# STM32.net
KiCad netlist of a schematic drawn in Altium Designer
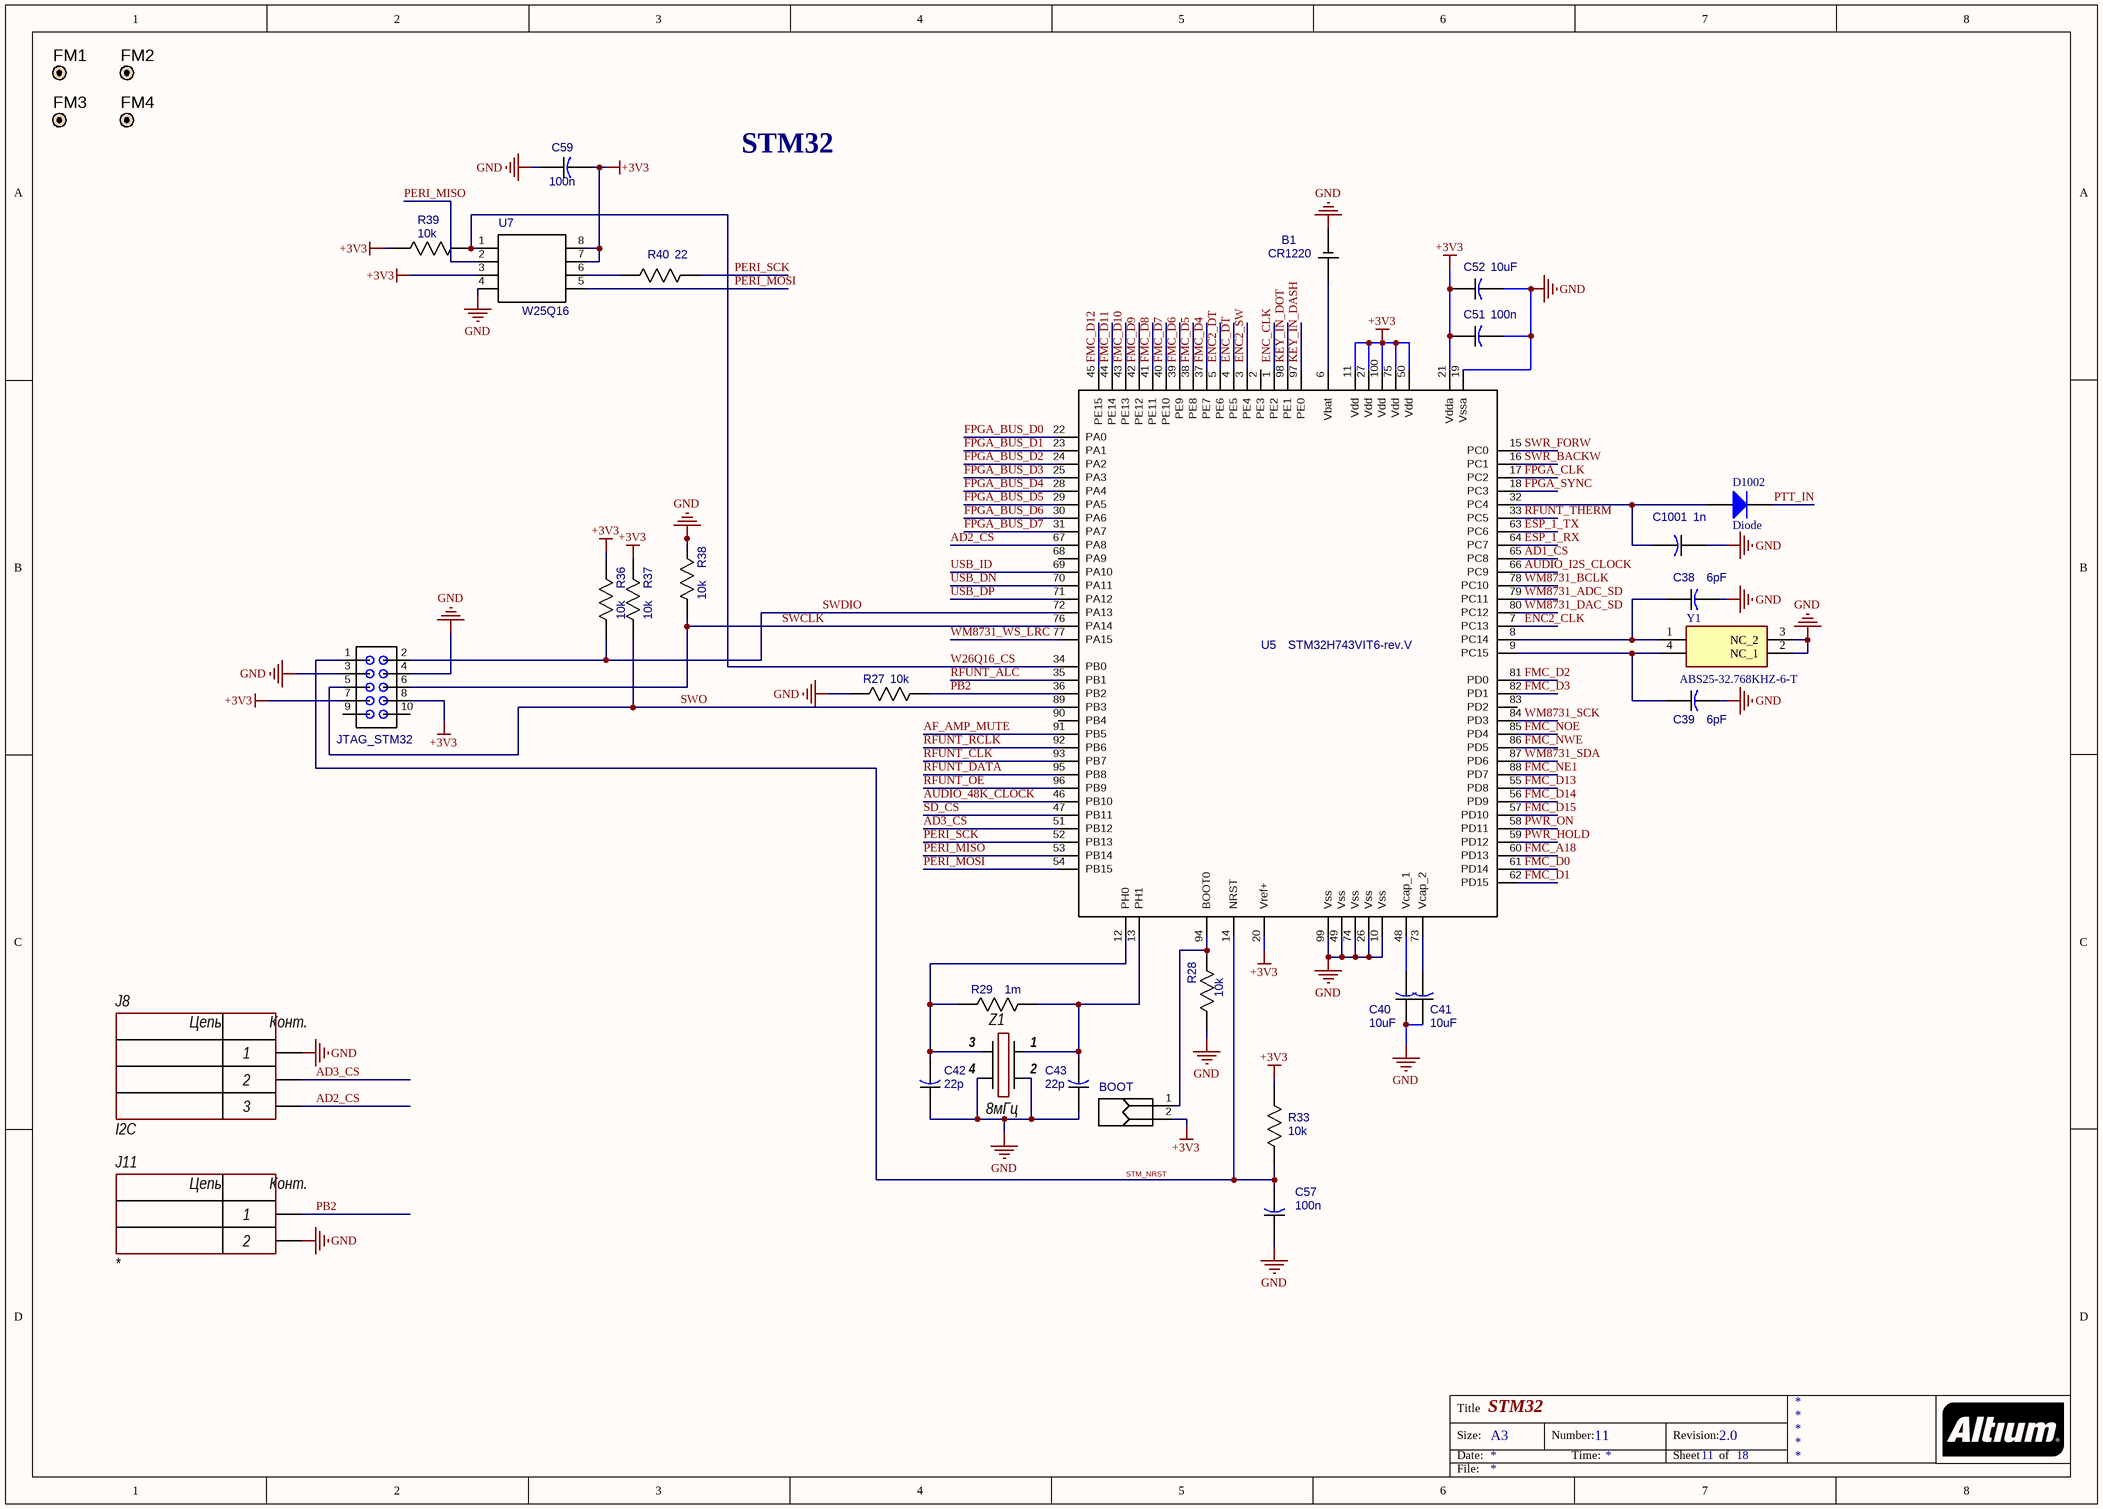
[diagram p0: STM32.SchDoc]

(export (version "E")
  (design (tool "Eeschema 10.0.6"))
  (components
    (comp (ref "B1")
      (value "CR1220")
      (footprint "CR1220")
      (description "BR1632A/FA")
      (fields (field (name "Comment") "CR1220 +"))
      (libsource (lib "*") (part "BR1632A/FA"))
    )
    (comp (ref "BOOT")
      (value "~")
      (footprint "51022-0200")
      (description "2 Pin")
      (libsource (lib "*") (part "51022-0200"))
    )
    (comp (ref "C38")
      (value "6pF")
      (footprint "CAP_0805")
      (description "CAP_0805")
      (libsource (lib "*") (part "CAP_0805"))
    )
    (comp (ref "C39")
      (value "6pF")
      (footprint "CAP_0805")
      (description "CAP_0805")
      (libsource (lib "*") (part "CAP_0805"))
    )
    (comp (ref "C40")
      (value "10uF")
      (footprint "CAP_0805")
      (description "CAP_0805")
      (libsource (lib "*") (part "CAP_0805"))
    )
    (comp (ref "C41")
      (value "10uF")
      (footprint "CAP_0805")
      (description "CAP_0805")
      (libsource (lib "*") (part "CAP_0805"))
    )
    (comp (ref "C42")
      (value "22p")
      (footprint "CH0805C")
      (description "CAP_0805")
      (libsource (lib "*") (part "CAP_0805"))
    )
    (comp (ref "C43")
      (value "22p")
      (footprint "CH0805C")
      (description "CAP_0805")
      (libsource (lib "*") (part "CAP_0805"))
    )
    (comp (ref "C51")
      (value "100n")
      (footprint "CAP_0805")
      (description "CAP_0805")
      (libsource (lib "*") (part "CAP_0805"))
    )
    (comp (ref "C52")
      (value "10uF")
      (footprint "CAP_0805")
      (description "CAP_0805")
      (libsource (lib "*") (part "CAP_0805"))
    )
    (comp (ref "C57")
      (value "100n")
      (footprint "CAP_0805")
      (description "CAP_0805")
      (libsource (lib "*") (part "CAP_0805"))
    )
    (comp (ref "C59")
      (value "100n")
      (footprint "CAP_0805")
      (description "CAP_0805")
      (libsource (lib "*") (part "CAP_0805"))
    )
    (comp (ref "C1001")
      (value "1n")
      (footprint "CAP_0805")
      (description "CAP_0805")
      (libsource (lib "*") (part "CAP_0805"))
    )
    (comp (ref "D1002")
      (value "Diode")
      (footprint "C1206")
      (description "Default Diode")
      (fields (field (name "PUBLISHER") "Altium Limited"))
      (libsource (lib "Miscellaneous Devices") (part "Diode"))
    )
    (comp (ref "FM1") (value "FM1") (footprint "FM") (libsource (lib "Connectors") (part "FM")))
    (comp (ref "FM2") (value "FM1") (footprint "FM") (libsource (lib "Connectors") (part "FM")))
    (comp (ref "FM3") (value "FM1") (footprint "FM") (libsource (lib "Connectors") (part "FM")))
    (comp (ref "FM4") (value "FM1") (footprint "FM") (libsource (lib "Connectors") (part "FM")))
    (comp (ref "J8")
      (value "I2C")
      (footprint "custom:CON: CWF-3")
      (libsource (lib "Connectors") (part "3-Connector"))
    )
    (comp (ref "J11")
      (value "*")
      (footprint "custom:CON: CWF-2")
      (libsource (lib "Connectors") (part "2-Connector"))
    )
    (comp (ref "JTAG_STM32")
      (value "~")
      (footprint "IDC10")
      (description "2*5 Pin")
      (libsource (lib "*") (part "IDC10"))
    )
    (comp (ref "R27")
      (value "10k")
      (footprint "RES_0805")
      (description "RES_0805")
      (libsource (lib "*") (part "RES_0805"))
    )
    (comp (ref "R28")
      (value "10k")
      (footprint "RES_0805")
      (description "RES_0805")
      (libsource (lib "*") (part "RES_0805"))
    )
    (comp (ref "R29")
      (value "1m")
      (footprint "RES_0805")
      (description "RES_0805")
      (libsource (lib "*") (part "RES_0805"))
    )
    (comp (ref "R33")
      (value "10k")
      (footprint "RES_0805")
      (description "RES_0805")
      (libsource (lib "*") (part "RES_0805"))
    )
    (comp (ref "R36")
      (value "10k")
      (footprint "RES_0805")
      (description "RES_0805")
      (libsource (lib "*") (part "RES_0805"))
    )
    (comp (ref "R37")
      (value "10k")
      (footprint "RES_0805")
      (description "RES_0805")
      (libsource (lib "*") (part "RES_0805"))
    )
    (comp (ref "R38")
      (value "10k")
      (footprint "RES_0805")
      (description "RES_0805")
      (libsource (lib "*") (part "RES_0805"))
    )
    (comp (ref "R39")
      (value "10k")
      (footprint "RES_0805")
      (description "RES_0805")
      (libsource (lib "*") (part "RES_0805"))
    )
    (comp (ref "R40")
      (value "22")
      (footprint "RES_0805")
      (description "RES_0805")
      (libsource (lib "*") (part "RES_0805"))
    )
    (comp (ref "U5")
      (value "STM32H743VIT6-rev.V")
      (footprint "STM32H743VIT6")
      (description "STM32H743VIT6")
      (libsource (lib "*") (part "STM32H743VIT6"))
    )
    (comp (ref "U7") (value "W25Q16") (footprint "SOIC-8-1") (libsource (lib "*") (part "W25Q16")))
    (comp (ref "Y1")
      (value "ABS25-32.768KHZ-6-T")
      (footprint "SamacSys:ABS25")
      (description "Crystal or Oscillator")
      (fields
        (field (name "MOUSER PART NUMBER") "815-ABS25-32.768K6-T")
        (field (name "RS PART NUMBER") "1712795P")
      )
      (libsource (lib "*") (part "ABS25-32.768KHZ-6-T"))
    )
    (comp (ref "Z1")
      (value "8мГц")
      (footprint "custom:OSC: 3225")
      (libsource (lib "Discrete") (part "Generator"))
    )
  )
  (nets
    (net (code "1") (name "+3V3") (class "Default")
      (node (ref "BOOT") (pin "2") (pinfunction "2_2") (pintype "passive"))
      (node (ref "C51") (pin "1") (pinfunction "1_1") (pintype "passive"))
      (node (ref "C52") (pin "1") (pinfunction "1_1") (pintype "passive"))
      (node (ref "C59") (pin "2") (pinfunction "2_2") (pintype "passive"))
      (node (ref "JTAG_STM32") (pin "7") (pinfunction "7_7") (pintype "passive"))
      (node (ref "JTAG_STM32") (pin "8") (pinfunction "8_8") (pintype "passive"))
      (node (ref "R33") (pin "2") (pinfunction "2_2") (pintype "passive"))
      (node (ref "R36") (pin "1") (pinfunction "1_1") (pintype "passive"))
      (node (ref "R37") (pin "1") (pinfunction "1_1") (pintype "passive"))
      (node (ref "R39") (pin "1") (pinfunction "1_1") (pintype "passive"))
      (node (ref "U5") (pin "100") (pinfunction "Vdd_100") (pintype "passive"))
      (node (ref "U5") (pin "11") (pinfunction "Vdd_11") (pintype "passive"))
      (node (ref "U5") (pin "20") (pinfunction "Vref+_20") (pintype "passive"))
      (node (ref "U5") (pin "21") (pinfunction "Vdda_21") (pintype "passive"))
      (node (ref "U5") (pin "27") (pinfunction "Vdd_27") (pintype "passive"))
      (node (ref "U5") (pin "50") (pinfunction "Vdd_50") (pintype "passive"))
      (node (ref "U5") (pin "75") (pinfunction "Vdd_75") (pintype "passive"))
      (node (ref "U7") (pin "3") (pinfunction "WP_3") (pintype "passive"))
      (node (ref "U7") (pin "7") (pinfunction "HOLD_7") (pintype "passive"))
      (node (ref "U7") (pin "8") (pinfunction "VCC_8") (pintype "passive"))
    )
    (net (code "2") (name "/AD1_CS") (class "Default")
      (node (ref "U5") (pin "65") (pinfunction "PC8_65") (pintype "passive"))
    )
    (net (code "3") (name "/AD2_CS") (class "Default")
      (node (ref "J8") (pin "3") (pinfunction "3_3") (pintype "power_in"))
      (node (ref "U5") (pin "67") (pinfunction "PA8_67") (pintype "passive"))
    )
    (net (code "4") (name "/AD3_CS") (class "Default")
      (node (ref "J8") (pin "2") (pinfunction "2_2") (pintype "passive"))
      (node (ref "U5") (pin "51") (pinfunction "PB12_51") (pintype "passive"))
    )
    (net (code "5") (name "/AF_AMP_MUTE") (class "Default")
      (node (ref "U5") (pin "91") (pinfunction "PB5_91") (pintype "passive"))
    )
    (net (code "6") (name "/AUDIO_48K_CLOCK") (class "Default")
      (node (ref "U5") (pin "46") (pinfunction "PB10_46") (pintype "passive"))
    )
    (net (code "7") (name "/AUDIO_I2S_CLOCK") (class "Default")
      (node (ref "U5") (pin "66") (pinfunction "PC9_66") (pintype "passive"))
    )
    (net (code "8") (name "/ENC2_CLK") (class "Default")
      (node (ref "U5") (pin "7") (pinfunction "PC13_7") (pintype "passive"))
    )
    (net (code "9") (name "/ENC2_DT") (class "Default")
      (node (ref "U5") (pin "5") (pinfunction "PE6_5") (pintype "passive"))
    )
    (net (code "10") (name "/ENC2_SW") (class "Default")
      (node (ref "U5") (pin "3") (pinfunction "PE4_3") (pintype "passive"))
    )
    (net (code "11") (name "/ENC_CLK") (class "Default")
      (node (ref "U5") (pin "1") (pinfunction "PE2_1") (pintype "passive"))
    )
    (net (code "12") (name "/ENC_DT") (class "Default")
      (node (ref "U5") (pin "4") (pinfunction "PE5_4") (pintype "passive"))
    )
    (net (code "13") (name "/ESP_1_RX") (class "Default")
      (node (ref "U5") (pin "64") (pinfunction "PC7_64") (pintype "passive"))
    )
    (net (code "14") (name "/ESP_1_TX") (class "Default")
      (node (ref "U5") (pin "63") (pinfunction "PC6_63") (pintype "passive"))
    )
    (net (code "15") (name "/FMC_A18") (class "Default")
      (node (ref "U5") (pin "60") (pinfunction "PD13_60") (pintype "passive"))
    )
    (net (code "16") (name "/FMC_D0") (class "Default")
      (node (ref "U5") (pin "61") (pinfunction "PD14_61") (pintype "passive"))
    )
    (net (code "17") (name "/FMC_D1") (class "Default")
      (node (ref "U5") (pin "62") (pinfunction "PD15_62") (pintype "passive"))
    )
    (net (code "18") (name "/FMC_D2") (class "Default")
      (node (ref "U5") (pin "81") (pinfunction "PD0_81") (pintype "passive"))
    )
    (net (code "19") (name "/FMC_D3") (class "Default")
      (node (ref "U5") (pin "82") (pinfunction "PD1_82") (pintype "passive"))
    )
    (net (code "20") (name "/FMC_D4") (class "Default")
      (node (ref "U5") (pin "37") (pinfunction "PE7_37") (pintype "passive"))
    )
    (net (code "21") (name "/FMC_D5") (class "Default")
      (node (ref "U5") (pin "38") (pinfunction "PE8_38") (pintype "passive"))
    )
    (net (code "22") (name "/FMC_D6") (class "Default")
      (node (ref "U5") (pin "39") (pinfunction "PE9_39") (pintype "passive"))
    )
    (net (code "23") (name "/FMC_D7") (class "Default")
      (node (ref "U5") (pin "40") (pinfunction "PE10_40") (pintype "passive"))
    )
    (net (code "24") (name "/FMC_D8") (class "Default")
      (node (ref "U5") (pin "41") (pinfunction "PE11_41") (pintype "passive"))
    )
    (net (code "25") (name "/FMC_D9") (class "Default")
      (node (ref "U5") (pin "42") (pinfunction "PE12_42") (pintype "passive"))
    )
    (net (code "26") (name "/FMC_D10") (class "Default")
      (node (ref "U5") (pin "43") (pinfunction "PE13_43") (pintype "passive"))
    )
    (net (code "27") (name "/FMC_D11") (class "Default")
      (node (ref "U5") (pin "44") (pinfunction "PE14_44") (pintype "passive"))
    )
    (net (code "28") (name "/FMC_D12") (class "Default")
      (node (ref "U5") (pin "45") (pinfunction "PE15_45") (pintype "passive"))
    )
    (net (code "29") (name "/FMC_D13") (class "Default")
      (node (ref "U5") (pin "55") (pinfunction "PD8_55") (pintype "passive"))
    )
    (net (code "30") (name "/FMC_D14") (class "Default")
      (node (ref "U5") (pin "56") (pinfunction "PD9_56") (pintype "passive"))
    )
    (net (code "31") (name "/FMC_D15") (class "Default")
      (node (ref "U5") (pin "57") (pinfunction "PD10_57") (pintype "passive"))
    )
    (net (code "32") (name "/FMC_NE1") (class "Default")
      (node (ref "U5") (pin "88") (pinfunction "PD7_88") (pintype "passive"))
    )
    (net (code "33") (name "/FMC_NOE") (class "Default")
      (node (ref "U5") (pin "85") (pinfunction "PD4_85") (pintype "passive"))
    )
    (net (code "34") (name "/FMC_NWE") (class "Default")
      (node (ref "U5") (pin "86") (pinfunction "PD5_86") (pintype "passive"))
    )
    (net (code "35") (name "/FPGA_BUS_D0") (class "Default")
      (node (ref "U5") (pin "22") (pinfunction "PA0_22") (pintype "passive"))
    )
    (net (code "36") (name "/FPGA_BUS_D1") (class "Default")
      (node (ref "U5") (pin "23") (pinfunction "PA1_23") (pintype "passive"))
    )
    (net (code "37") (name "/FPGA_BUS_D2") (class "Default")
      (node (ref "U5") (pin "24") (pinfunction "PA2_24") (pintype "passive"))
    )
    (net (code "38") (name "/FPGA_BUS_D3") (class "Default")
      (node (ref "U5") (pin "25") (pinfunction "PA3_25") (pintype "passive"))
    )
    (net (code "39") (name "/FPGA_BUS_D4") (class "Default")
      (node (ref "U5") (pin "28") (pinfunction "PA4_28") (pintype "passive"))
    )
    (net (code "40") (name "/FPGA_BUS_D5") (class "Default")
      (node (ref "U5") (pin "29") (pinfunction "PA5_29") (pintype "passive"))
    )
    (net (code "41") (name "/FPGA_BUS_D6") (class "Default")
      (node (ref "U5") (pin "30") (pinfunction "PA6_30") (pintype "passive"))
    )
    (net (code "42") (name "/FPGA_BUS_D7") (class "Default")
      (node (ref "U5") (pin "31") (pinfunction "PA7_31") (pintype "passive"))
    )
    (net (code "43") (name "/FPGA_CLK") (class "Default")
      (node (ref "U5") (pin "17") (pinfunction "PC2_17") (pintype "passive"))
    )
    (net (code "44") (name "/FPGA_SYNC") (class "Default")
      (node (ref "U5") (pin "18") (pinfunction "PC3_18") (pintype "passive"))
    )
    (net (code "45") (name "/KEY_IN_DASH") (class "Default")
      (node (ref "U5") (pin "97") (pinfunction "PE0_97") (pintype "passive"))
    )
    (net (code "46") (name "/KEY_IN_DOT") (class "Default")
      (node (ref "U5") (pin "98") (pinfunction "PE1_98") (pintype "passive"))
    )
    (net (code "47") (name "/PB2") (class "Default")
      (node (ref "J11") (pin "1") (pinfunction "1_1") (pintype "passive"))
      (node (ref "R27") (pin "2") (pinfunction "2_2") (pintype "passive"))
      (node (ref "U5") (pin "36") (pinfunction "PB2_36") (pintype "passive"))
    )
    (net (code "48") (name "/PERI_MISO") (class "Default")
      (node (ref "U5") (pin "53") (pinfunction "PB14_53") (pintype "passive"))
      (node (ref "U7") (pin "2") (pinfunction "SO_2") (pintype "passive"))
    )
    (net (code "49") (name "/PERI_MOSI") (class "Default")
      (node (ref "U5") (pin "54") (pinfunction "PB15_54") (pintype "passive"))
      (node (ref "U7") (pin "5") (pinfunction "SI_5") (pintype "passive"))
    )
    (net (code "50") (name "/PERI_SCK") (class "Default")
      (node (ref "R40") (pin "2") (pinfunction "2_2") (pintype "passive"))
      (node (ref "U5") (pin "52") (pinfunction "PB13_52") (pintype "passive"))
    )
    (net (code "51") (name "/PTT_IN") (class "Default")
      (node (ref "D1002") (pin "2") (pinfunction "K_2") (pintype "passive"))
    )
    (net (code "52") (name "/PWR_HOLD") (class "Default")
      (node (ref "U5") (pin "59") (pinfunction "PD12_59") (pintype "passive"))
    )
    (net (code "53") (name "/PWR_ON") (class "Default")
      (node (ref "U5") (pin "58") (pinfunction "PD11_58") (pintype "passive"))
    )
    (net (code "54") (name "/RFUNT_ALC") (class "Default")
      (node (ref "U5") (pin "35") (pinfunction "PB1_35") (pintype "passive"))
    )
    (net (code "55") (name "/RFUNT_CLK") (class "Default")
      (node (ref "U5") (pin "93") (pinfunction "PB7_93") (pintype "passive"))
    )
    (net (code "56") (name "/RFUNT_DATA") (class "Default")
      (node (ref "U5") (pin "95") (pinfunction "PB8_95") (pintype "passive"))
    )
    (net (code "57") (name "/RFUNT_OE") (class "Default")
      (node (ref "U5") (pin "96") (pinfunction "PB9_96") (pintype "passive"))
    )
    (net (code "58") (name "/RFUNT_RCLK") (class "Default")
      (node (ref "U5") (pin "92") (pinfunction "PB6_92") (pintype "passive"))
    )
    (net (code "59") (name "/RFUNT_THERM") (class "Default")
      (node (ref "U5") (pin "33") (pinfunction "PC5_33") (pintype "passive"))
    )
    (net (code "60") (name "/SD_CS") (class "Default")
      (node (ref "U5") (pin "47") (pinfunction "PB11_47") (pintype "passive"))
    )
    (net (code "61") (name "/STM_NRST") (class "Default")
      (node (ref "C57") (pin "2") (pinfunction "2_2") (pintype "passive"))
      (node (ref "JTAG_STM32") (pin "1") (pinfunction "1_1") (pintype "passive"))
      (node (ref "R33") (pin "1") (pinfunction "1_1") (pintype "passive"))
      (node (ref "U5") (pin "14") (pinfunction "NRST_14") (pintype "passive"))
    )
    (net (code "62") (name "/SWCLK") (class "Default")
      (node (ref "JTAG_STM32") (pin "6") (pinfunction "6_6") (pintype "passive"))
      (node (ref "R38") (pin "2") (pinfunction "2_2") (pintype "passive"))
      (node (ref "U5") (pin "76") (pinfunction "PA14_76") (pintype "passive"))
    )
    (net (code "63") (name "/SWDIO") (class "Default")
      (node (ref "JTAG_STM32") (pin "2") (pinfunction "2_2") (pintype "passive"))
      (node (ref "R36") (pin "2") (pinfunction "2_2") (pintype "passive"))
      (node (ref "U5") (pin "72") (pinfunction "PA13_72") (pintype "passive"))
    )
    (net (code "64") (name "/SWO") (class "Default")
      (node (ref "JTAG_STM32") (pin "5") (pinfunction "5_5") (pintype "passive"))
      (node (ref "R37") (pin "2") (pinfunction "2_2") (pintype "passive"))
      (node (ref "U5") (pin "89") (pinfunction "PB3_89") (pintype "passive"))
    )
    (net (code "65") (name "/SWR_BACKW") (class "Default")
      (node (ref "U5") (pin "16") (pinfunction "PC1_16") (pintype "passive"))
    )
    (net (code "66") (name "/SWR_FORW") (class "Default")
      (node (ref "U5") (pin "15") (pinfunction "PC0_15") (pintype "passive"))
    )
    (net (code "67") (name "/USB_DN") (class "Default")
      (node (ref "U5") (pin "70") (pinfunction "PA11_70") (pintype "passive"))
    )
    (net (code "68") (name "/USB_DP") (class "Default")
      (node (ref "U5") (pin "71") (pinfunction "PA12_71") (pintype "passive"))
    )
    (net (code "69") (name "/USB_ID") (class "Default")
      (node (ref "U5") (pin "69") (pinfunction "PA10_69") (pintype "passive"))
    )
    (net (code "70") (name "/W26Q16_CS") (class "Default")
      (node (ref "R39") (pin "2") (pinfunction "2_2") (pintype "passive"))
      (node (ref "U5") (pin "34") (pinfunction "PB0_34") (pintype "passive"))
      (node (ref "U7") (pin "1") (pinfunction "CS_1") (pintype "passive"))
    )
    (net (code "71") (name "/WM8731_ADC_SD") (class "Default")
      (node (ref "U5") (pin "79") (pinfunction "PC11_79") (pintype "passive"))
    )
    (net (code "72") (name "/WM8731_BCLK") (class "Default")
      (node (ref "U5") (pin "78") (pinfunction "PC10_78") (pintype "passive"))
    )
    (net (code "73") (name "/WM8731_DAC_SD") (class "Default")
      (node (ref "U5") (pin "80") (pinfunction "PC12_80") (pintype "passive"))
    )
    (net (code "74") (name "/WM8731_SCK") (class "Default")
      (node (ref "U5") (pin "84") (pinfunction "PD3_84") (pintype "passive"))
    )
    (net (code "75") (name "/WM8731_SDA") (class "Default")
      (node (ref "U5") (pin "87") (pinfunction "PD6_87") (pintype "passive"))
    )
    (net (code "76") (name "/WM8731_WS_LRC") (class "Default")
      (node (ref "U5") (pin "77") (pinfunction "PA15_77") (pintype "passive"))
    )
    (net (code "77") (name "GND") (class "Default")
      (node (ref "B1") (pin "2") (pinfunction "NEG_2") (pintype "passive"))
      (node (ref "C1001") (pin "1") (pinfunction "1_1") (pintype "passive"))
      (node (ref "C38") (pin "2") (pinfunction "2_2") (pintype "passive"))
      (node (ref "C39") (pin "2") (pinfunction "2_2") (pintype "passive"))
      (node (ref "C40") (pin "1") (pinfunction "1_1") (pintype "passive"))
      (node (ref "C41") (pin "1") (pinfunction "1_1") (pintype "passive"))
      (node (ref "C42") (pin "1") (pinfunction "1_1") (pintype "passive"))
      (node (ref "C43") (pin "1") (pinfunction "1_1") (pintype "passive"))
      (node (ref "C51") (pin "2") (pinfunction "2_2") (pintype "passive"))
      (node (ref "C52") (pin "2") (pinfunction "2_2") (pintype "passive"))
      (node (ref "C57") (pin "1") (pinfunction "1_1") (pintype "passive"))
      (node (ref "C59") (pin "1") (pinfunction "1_1") (pintype "passive"))
      (node (ref "J11") (pin "2") (pinfunction "2_2") (pintype "passive"))
      (node (ref "J8") (pin "1") (pinfunction "1_1") (pintype "passive"))
      (node (ref "JTAG_STM32") (pin "3") (pinfunction "3_3") (pintype "passive"))
      (node (ref "JTAG_STM32") (pin "4") (pinfunction "4_4") (pintype "passive"))
      (node (ref "R27") (pin "1") (pinfunction "1_1") (pintype "passive"))
      (node (ref "R28") (pin "1") (pinfunction "1_1") (pintype "passive"))
      (node (ref "R38") (pin "1") (pinfunction "1_1") (pintype "passive"))
      (node (ref "U5") (pin "10") (pinfunction "Vss_10") (pintype "passive"))
      (node (ref "U5") (pin "19") (pinfunction "Vssa_19") (pintype "passive"))
      (node (ref "U5") (pin "26") (pinfunction "Vss_26") (pintype "passive"))
      (node (ref "U5") (pin "49") (pinfunction "Vss_49") (pintype "passive"))
      (node (ref "U5") (pin "74") (pinfunction "Vss_74") (pintype "passive"))
      (node (ref "U5") (pin "99") (pinfunction "Vss_99") (pintype "passive"))
      (node (ref "U7") (pin "4") (pinfunction "GND_4") (pintype "passive"))
      (node (ref "Y1") (pin "2") (pinfunction "NC_1_2") (pintype "passive"))
      (node (ref "Y1") (pin "3") (pinfunction "NC_2_3") (pintype "passive"))
      (node (ref "Z1") (pin "2") (pinfunction "2_2") (pintype "passive"))
      (node (ref "Z1") (pin "4") (pinfunction "4_4") (pintype "passive"))
    )
    (net (code "78") (name "Net-(B1-POS)") (class "Default")
      (node (ref "B1") (pin "1") (pinfunction "POS_1") (pintype "passive"))
      (node (ref "U5") (pin "6") (pinfunction "Vbat_6") (pintype "passive"))
    )
    (net (code "79") (name "Net-(D1002-A)") (class "Default")
      (node (ref "C1001") (pin "2") (pinfunction "2_2") (pintype "passive"))
      (node (ref "D1002") (pin "1") (pinfunction "A_1") (pintype "passive"))
      (node (ref "U5") (pin "32") (pinfunction "PC4_32") (pintype "passive"))
    )
    (net (code "80") (name "Net-(U5-BOOT0)") (class "Default")
      (node (ref "BOOT") (pin "1") (pinfunction "1_1") (pintype "passive"))
      (node (ref "R28") (pin "2") (pinfunction "2_2") (pintype "passive"))
      (node (ref "U5") (pin "94") (pinfunction "BOOT0_94") (pintype "passive"))
    )
    (net (code "81") (name "Net-(U5-PC14)") (class "Default")
      (node (ref "C38") (pin "1") (pinfunction "1_1") (pintype "passive"))
      (node (ref "U5") (pin "8") (pinfunction "PC14_8") (pintype "passive"))
      (node (ref "Y1") (pin "1") (pinfunction "1_1") (pintype "passive"))
    )
    (net (code "82") (name "Net-(U5-PC15)") (class "Default")
      (node (ref "C39") (pin "1") (pinfunction "1_1") (pintype "passive"))
      (node (ref "U5") (pin "9") (pinfunction "PC15_9") (pintype "passive"))
      (node (ref "Y1") (pin "4") (pinfunction "4_4") (pintype "passive"))
    )
    (net (code "83") (name "Net-(U5-PH0)") (class "Default")
      (node (ref "C42") (pin "2") (pinfunction "2_2") (pintype "passive"))
      (node (ref "R29") (pin "1") (pinfunction "1_1") (pintype "passive"))
      (node (ref "U5") (pin "12") (pinfunction "PH0_12") (pintype "passive"))
      (node (ref "Z1") (pin "3") (pinfunction "3_3") (pintype "passive"))
    )
    (net (code "84") (name "Net-(U5-PH1)") (class "Default")
      (node (ref "C43") (pin "2") (pinfunction "2_2") (pintype "passive"))
      (node (ref "R29") (pin "2") (pinfunction "2_2") (pintype "passive"))
      (node (ref "U5") (pin "13") (pinfunction "PH1_13") (pintype "passive"))
      (node (ref "Z1") (pin "1") (pinfunction "1_1") (pintype "passive"))
    )
    (net (code "85") (name "Net-(U5-Vcap_1)") (class "Default")
      (node (ref "C40") (pin "2") (pinfunction "2_2") (pintype "passive"))
      (node (ref "U5") (pin "48") (pinfunction "Vcap_1_48") (pintype "passive"))
    )
    (net (code "86") (name "Net-(U5-Vcap_2)") (class "Default")
      (node (ref "C41") (pin "2") (pinfunction "2_2") (pintype "passive"))
      (node (ref "U5") (pin "73") (pinfunction "Vcap_2_73") (pintype "passive"))
    )
    (net (code "87") (name "Net-(U7-CLK)") (class "Default")
      (node (ref "R40") (pin "1") (pinfunction "1_1") (pintype "passive"))
      (node (ref "U7") (pin "6") (pinfunction "CLK_6") (pintype "passive"))
    )
    (net (code "88") (name "unconnected-(JTAG_STM32-Pad9)") (class "Default")
      (node (ref "JTAG_STM32") (pin "9") (pinfunction "9_9") (pintype "passive"))
    )
    (net (code "89") (name "unconnected-(JTAG_STM32-Pad10)") (class "Default")
      (node (ref "JTAG_STM32") (pin "10") (pinfunction "10_10") (pintype "passive"))
    )
    (net (code "90") (name "unconnected-(U5-PA9-Pad68)") (class "Default")
      (node (ref "U5") (pin "68") (pinfunction "PA9_68") (pintype "passive"))
    )
    (net (code "91") (name "unconnected-(U5-PB4-Pad90)") (class "Default")
      (node (ref "U5") (pin "90") (pinfunction "PB4_90") (pintype "passive"))
    )
    (net (code "92") (name "unconnected-(U5-PD2-Pad83)") (class "Default")
      (node (ref "U5") (pin "83") (pinfunction "PD2_83") (pintype "passive"))
    )
    (net (code "93") (name "unconnected-(U5-PE3-Pad2)") (class "Default")
      (node (ref "U5") (pin "2") (pinfunction "PE3_2") (pintype "passive"))
    )
  )
)
